# RAM_v3.net
KiCad netlist of a schematic drawn in Altium Designer
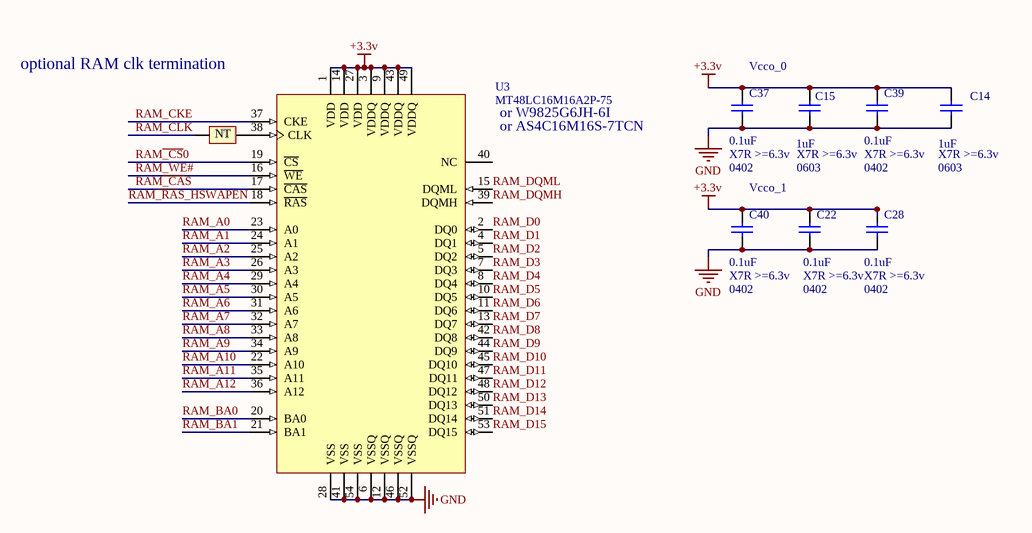
[diagram p0: RAM v3.SchDoc]

(export (version "E")
  (design (tool "Eeschema 10.0.6"))
  (components
    (comp (ref "C14")
      (value "1uF")
      (footprint "Chip_Capacitor_N:CAPC1608N")
      (description "Capacitor (Semiconductor SIM Model)")
      (fields
        (field (name "PACKAGEREFERENCE") "0603")
        (field (name "RATING") "X7R >=6.3v")
        (field (name "Comment") "Cap Semi")
      )
      (libsource (lib "Miscellaneous Devices") (part "Cap Semi"))
    )
    (comp (ref "C15")
      (value "1uF")
      (footprint "Chip_Capacitor_N:CAPC1608N")
      (description "Capacitor (Semiconductor SIM Model)")
      (fields
        (field (name "PACKAGEREFERENCE") "0603")
        (field (name "RATING") "X7R >=6.3v")
        (field (name "Comment") "Cap Semi")
      )
      (libsource (lib "Miscellaneous Devices") (part "Cap Semi"))
    )
    (comp (ref "C22")
      (value "0.1uF")
      (footprint "CAPC1005N")
      (description "CAP CER 0.1UF 25V 10% X5R 0603")
      (fields
        (field (name "PACKAGEREFERENCE") "0402")
        (field (name "TOLERANCE") "±10%")
        (field (name "RATING") "X7R >=6.3v")
      )
      (libsource (lib "Miscellaneous Devices") (part "Cap Semi"))
    )
    (comp (ref "C28")
      (value "0.1uF")
      (footprint "CAPC1005N")
      (description "CAP CER 0.1UF 25V 10% X5R 0603")
      (fields
        (field (name "PACKAGEREFERENCE") "0402")
        (field (name "TOLERANCE") "±10%")
        (field (name "RATING") "X7R >=6.3v")
      )
      (libsource (lib "Miscellaneous Devices") (part "Cap Semi"))
    )
    (comp (ref "C37")
      (value "0.1uF")
      (footprint "CAPC1005N")
      (description "Capacitor (Semiconductor SIM Model)")
      (fields
        (field (name "PACKAGEREFERENCE") "0402")
        (field (name "RATING") "X7R >=6.3v")
        (field (name "TOLERANCE") "±10%")
        (field (name "Comment") "Cap Semi")
      )
      (libsource (lib "Miscellaneous Devices") (part "Cap Semi"))
    )
    (comp (ref "C39")
      (value "0.1uF")
      (footprint "CAPC1005N")
      (description "Capacitor (Semiconductor SIM Model)")
      (fields
        (field (name "PACKAGEREFERENCE") "0402")
        (field (name "RATING") "X7R >=6.3v")
        (field (name "TOLERANCE") "±10%")
        (field (name "Comment") "Cap Semi")
      )
      (libsource (lib "Miscellaneous Devices") (part "Cap Semi"))
    )
    (comp (ref "C40")
      (value "0.1uF")
      (footprint "CAPC1005N")
      (description "CAP CER 0.1UF 25V 10% X5R 0603")
      (fields
        (field (name "PACKAGEREFERENCE") "0402")
        (field (name "TOLERANCE") "±10%")
        (field (name "RATING") "X7R >=6.3v")
      )
      (libsource (lib "Miscellaneous Devices") (part "Cap Semi"))
    )
    (comp (ref "NT1")
      (value "Net Tie2")
      (footprint "NetTie 0603")
      (description "0603 Net Tie to connect 2 different nets")
      (libsource (lib "OpenVizsla symbols") (part "Net Tie2"))
    )
    (comp (ref "U3")
      (value "MT48LC16M16A2P-75")
      (footprint "TSOP2-54_N")
      (description "256Mb Synchronous High-Speed CMOS DRAM, 16Mb x 16Bit x 4 Banks, 54-Pin TSOP Pb-free, Commercial")
      (libsource (lib "Micron Memory Dynamic RAM") (part "MT48LC16M16A2P-75"))
    )
  )
  (nets
    (net (code "1") (name "+3.3v") (class "Default")
      (node (ref "C14") (pin "2") (pinfunction "2_2") (pintype "passive"))
      (node (ref "C15") (pin "2") (pinfunction "2_2") (pintype "passive"))
      (node (ref "C22") (pin "2") (pinfunction "2_2") (pintype "passive"))
      (node (ref "C28") (pin "2") (pinfunction "2_2") (pintype "passive"))
      (node (ref "C37") (pin "2") (pinfunction "2_2") (pintype "passive"))
      (node (ref "C39") (pin "2") (pinfunction "2_2") (pintype "passive"))
      (node (ref "C40") (pin "2") (pinfunction "2_2") (pintype "passive"))
      (node (ref "U3") (pin "1") (pinfunction "VDD_1") (pintype "power_in"))
      (node (ref "U3") (pin "14") (pinfunction "VDD_14") (pintype "power_in"))
      (node (ref "U3") (pin "27") (pinfunction "VDD_27") (pintype "power_in"))
      (node (ref "U3") (pin "3") (pinfunction "VDDQ_3") (pintype "power_in"))
      (node (ref "U3") (pin "43") (pinfunction "VDDQ_43") (pintype "power_in"))
      (node (ref "U3") (pin "49") (pinfunction "VDDQ_49") (pintype "power_in"))
      (node (ref "U3") (pin "9") (pinfunction "VDDQ_9") (pintype "power_in"))
    )
    (net (code "2") (name "/RAM_A0") (class "Default")
      (node (ref "U3") (pin "23") (pinfunction "A0_23") (pintype "input"))
    )
    (net (code "3") (name "/RAM_A1") (class "Default")
      (node (ref "U3") (pin "24") (pinfunction "A1_24") (pintype "input"))
    )
    (net (code "4") (name "/RAM_A2") (class "Default")
      (node (ref "U3") (pin "25") (pinfunction "A2_25") (pintype "input"))
    )
    (net (code "5") (name "/RAM_A3") (class "Default")
      (node (ref "U3") (pin "26") (pinfunction "A3_26") (pintype "input"))
    )
    (net (code "6") (name "/RAM_A4") (class "Default")
      (node (ref "U3") (pin "29") (pinfunction "A4_29") (pintype "input"))
    )
    (net (code "7") (name "/RAM_A5") (class "Default")
      (node (ref "U3") (pin "30") (pinfunction "A5_30") (pintype "input"))
    )
    (net (code "8") (name "/RAM_A6") (class "Default")
      (node (ref "U3") (pin "31") (pinfunction "A6_31") (pintype "input"))
    )
    (net (code "9") (name "/RAM_A7") (class "Default")
      (node (ref "U3") (pin "32") (pinfunction "A7_32") (pintype "input"))
    )
    (net (code "10") (name "/RAM_A8") (class "Default")
      (node (ref "U3") (pin "33") (pinfunction "A8_33") (pintype "input"))
    )
    (net (code "11") (name "/RAM_A9") (class "Default")
      (node (ref "U3") (pin "34") (pinfunction "A9_34") (pintype "input"))
    )
    (net (code "12") (name "/RAM_A10") (class "Default")
      (node (ref "U3") (pin "22") (pinfunction "A10_22") (pintype "input"))
    )
    (net (code "13") (name "/RAM_A11") (class "Default")
      (node (ref "U3") (pin "35") (pinfunction "A11_35") (pintype "input"))
    )
    (net (code "14") (name "/RAM_A12") (class "Default")
      (node (ref "U3") (pin "36") (pinfunction "A12_36") (pintype "input"))
    )
    (net (code "15") (name "/RAM_BA0") (class "Default")
      (node (ref "U3") (pin "20") (pinfunction "BA0_20") (pintype "input"))
    )
    (net (code "16") (name "/RAM_BA1") (class "Default")
      (node (ref "U3") (pin "21") (pinfunction "BA1_21") (pintype "input"))
    )
    (net (code "17") (name "/RAM_CKE") (class "Default")
      (node (ref "U3") (pin "37") (pinfunction "CKE_37") (pintype "input"))
    )
    (net (code "18") (name "/RAM_CLK") (class "Default")
      (node (ref "NT1") (pin "1") (pinfunction "1_1") (pintype "passive"))
    )
    (net (code "19") (name "/RAM_D0") (class "Default")
      (node (ref "U3") (pin "2") (pinfunction "DQ0_2") (pintype "bidirectional"))
    )
    (net (code "20") (name "/RAM_D1") (class "Default")
      (node (ref "U3") (pin "4") (pinfunction "DQ1_4") (pintype "bidirectional"))
    )
    (net (code "21") (name "/RAM_D2") (class "Default")
      (node (ref "U3") (pin "5") (pinfunction "DQ2_5") (pintype "bidirectional"))
    )
    (net (code "22") (name "/RAM_D3") (class "Default")
      (node (ref "U3") (pin "7") (pinfunction "DQ3_7") (pintype "bidirectional"))
    )
    (net (code "23") (name "/RAM_D4") (class "Default")
      (node (ref "U3") (pin "8") (pinfunction "DQ4_8") (pintype "bidirectional"))
    )
    (net (code "24") (name "/RAM_D5") (class "Default")
      (node (ref "U3") (pin "10") (pinfunction "DQ5_10") (pintype "bidirectional"))
    )
    (net (code "25") (name "/RAM_D6") (class "Default")
      (node (ref "U3") (pin "11") (pinfunction "DQ6_11") (pintype "bidirectional"))
    )
    (net (code "26") (name "/RAM_D7") (class "Default")
      (node (ref "U3") (pin "13") (pinfunction "DQ7_13") (pintype "bidirectional"))
    )
    (net (code "27") (name "/RAM_D8") (class "Default")
      (node (ref "U3") (pin "42") (pinfunction "DQ8_42") (pintype "bidirectional"))
    )
    (net (code "28") (name "/RAM_D9") (class "Default")
      (node (ref "U3") (pin "44") (pinfunction "DQ9_44") (pintype "bidirectional"))
    )
    (net (code "29") (name "/RAM_D10") (class "Default")
      (node (ref "U3") (pin "45") (pinfunction "DQ10_45") (pintype "bidirectional"))
    )
    (net (code "30") (name "/RAM_D11") (class "Default")
      (node (ref "U3") (pin "47") (pinfunction "DQ11_47") (pintype "bidirectional"))
    )
    (net (code "31") (name "/RAM_D12") (class "Default")
      (node (ref "U3") (pin "48") (pinfunction "DQ12_48") (pintype "bidirectional"))
    )
    (net (code "32") (name "/RAM_D13") (class "Default")
      (node (ref "U3") (pin "50") (pinfunction "DQ13_50") (pintype "bidirectional"))
    )
    (net (code "33") (name "/RAM_D14") (class "Default")
      (node (ref "U3") (pin "51") (pinfunction "DQ14_51") (pintype "bidirectional"))
    )
    (net (code "34") (name "/RAM_D15") (class "Default")
      (node (ref "U3") (pin "53") (pinfunction "DQ15_53") (pintype "bidirectional"))
    )
    (net (code "35") (name "/RAM_DQMH") (class "Default")
      (node (ref "U3") (pin "39") (pinfunction "DQMH_39") (pintype "input"))
    )
    (net (code "36") (name "/RAM_DQML") (class "Default")
      (node (ref "U3") (pin "15") (pinfunction "DQML_15") (pintype "input"))
    )
    (net (code "37") (name "/RAM_WE#") (class "Default")
      (node (ref "U3") (pin "16") (pinfunction "~{WE}_16") (pintype "input"))
    )
    (net (code "38") (name "/RAM~{_CA}S") (class "Default")
      (node (ref "U3") (pin "17") (pinfunction "~{CAS}_17") (pintype "input"))
    )
    (net (code "39") (name "/RAM~{_CS}0") (class "Default")
      (node (ref "U3") (pin "19") (pinfunction "~{CS}_19") (pintype "input"))
    )
    (net (code "40") (name "/RAM~{_RA}S_HSWAPEN") (class "Default")
      (node (ref "U3") (pin "18") (pinfunction "~{RAS}_18") (pintype "input"))
    )
    (net (code "41") (name "GND") (class "Default")
      (node (ref "C14") (pin "1") (pinfunction "1_1") (pintype "passive"))
      (node (ref "C15") (pin "1") (pinfunction "1_1") (pintype "passive"))
      (node (ref "C22") (pin "1") (pinfunction "1_1") (pintype "passive"))
      (node (ref "C28") (pin "1") (pinfunction "1_1") (pintype "passive"))
      (node (ref "C37") (pin "1") (pinfunction "1_1") (pintype "passive"))
      (node (ref "C39") (pin "1") (pinfunction "1_1") (pintype "passive"))
      (node (ref "C40") (pin "1") (pinfunction "1_1") (pintype "passive"))
      (node (ref "U3") (pin "12") (pinfunction "VSSQ_12") (pintype "power_in"))
      (node (ref "U3") (pin "28") (pinfunction "VSS_28") (pintype "power_in"))
      (node (ref "U3") (pin "41") (pinfunction "VSS_41") (pintype "power_in"))
      (node (ref "U3") (pin "46") (pinfunction "VSSQ_46") (pintype "power_in"))
      (node (ref "U3") (pin "52") (pinfunction "VSSQ_52") (pintype "power_in"))
      (node (ref "U3") (pin "54") (pinfunction "VSS_54") (pintype "power_in"))
      (node (ref "U3") (pin "6") (pinfunction "VSSQ_6") (pintype "power_in"))
    )
    (net (code "42") (name "Net-(U3-CLK)") (class "Default")
      (node (ref "NT1") (pin "2") (pinfunction "2_2") (pintype "passive"))
      (node (ref "U3") (pin "38") (pinfunction "CLK_38") (pintype "input"))
    )
    (net (code "43") (name "unconnected-(U3-NC-Pad40)") (class "Default")
      (node (ref "U3") (pin "40") (pinfunction "NC_40") (pintype "passive"))
    )
  )
)
